# board.net
KiCad netlist of a schematic drawn in EAGLE
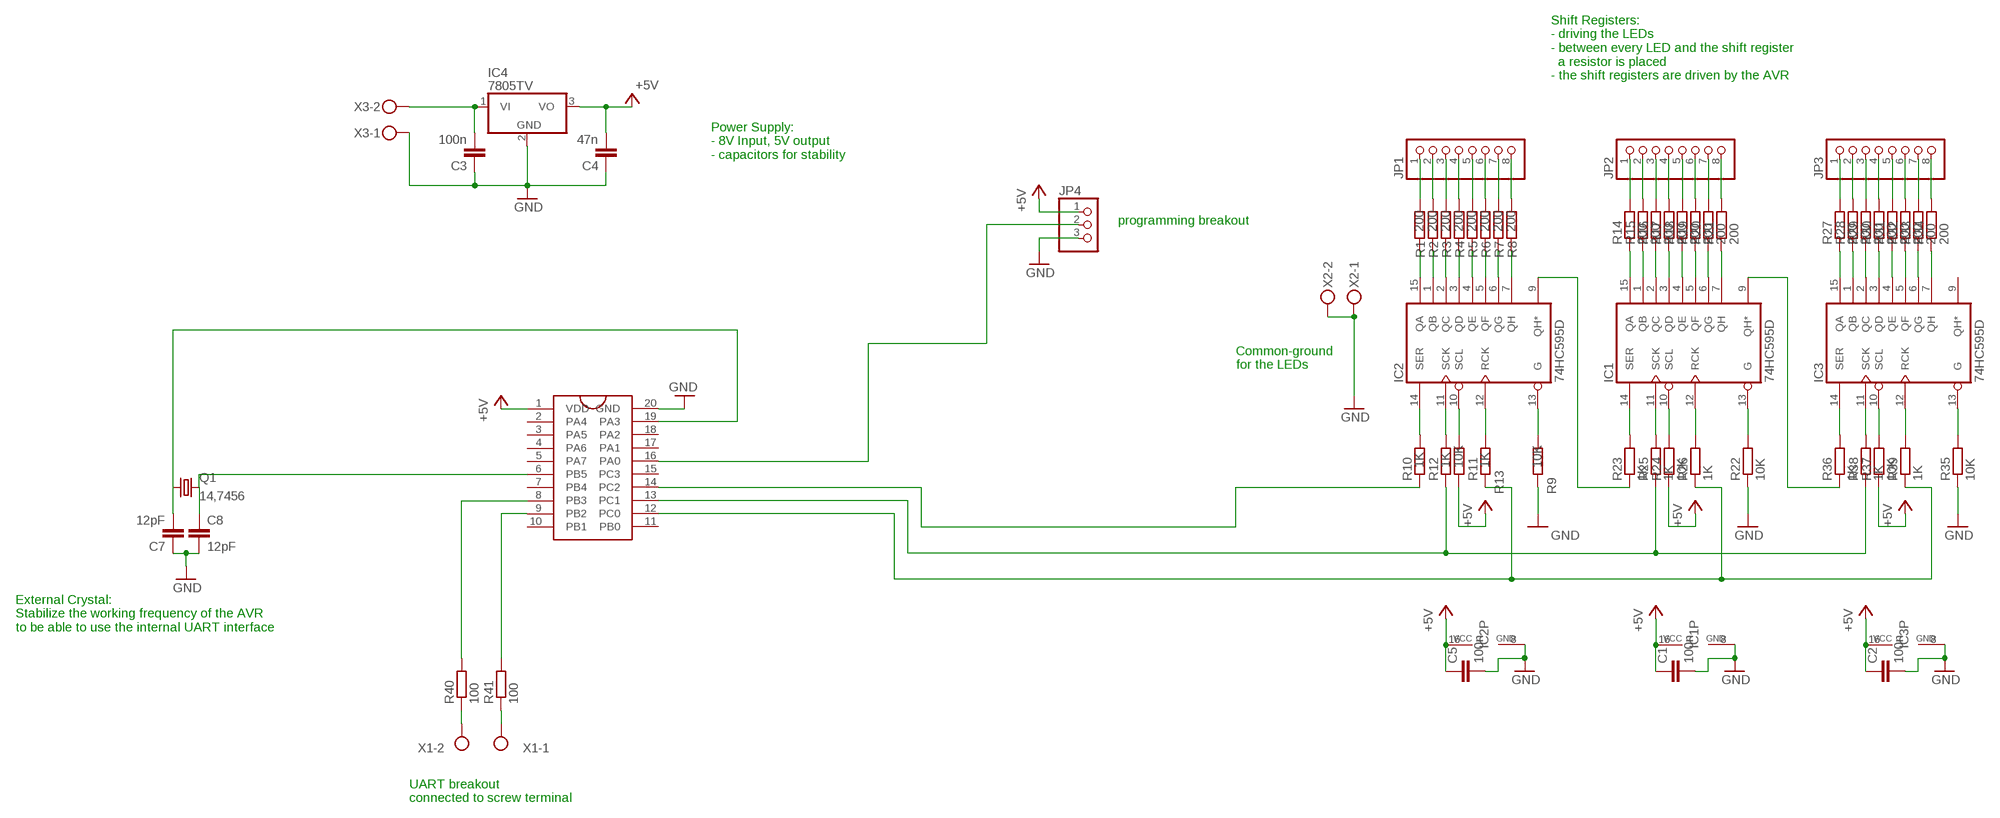
[diagram p0: schematic, sheet 1]

(export (version "E")
  (design (tool "Eeschema 10.0.6"))
  (components
    (comp (ref "C1")
      (value "100n")
      (footprint "eagle-import:C0805K")
      (libsource (lib "eagle-import") (part "C-EUC0805K"))
    )
    (comp (ref "C2")
      (value "100n")
      (footprint "eagle-import:C0805K")
      (libsource (lib "eagle-import") (part "C-EUC0805K"))
    )
    (comp (ref "C3")
      (value "100n")
      (footprint "eagle-import:C0805K")
      (libsource (lib "eagle-import") (part "C-EUC0805K"))
    )
    (comp (ref "C4")
      (value "47n")
      (footprint "eagle-import:C0805K")
      (libsource (lib "eagle-import") (part "C-EUC0805K"))
    )
    (comp (ref "C5")
      (value "100n")
      (footprint "eagle-import:C0805K")
      (libsource (lib "eagle-import") (part "C-EUC0805K"))
    )
    (comp (ref "C7")
      (value "12pF")
      (footprint "eagle-import:C0805K")
      (libsource (lib "eagle-import") (part "C-EUC0805K"))
    )
    (comp (ref "C8")
      (value "12pF")
      (footprint "eagle-import:C0805K")
      (libsource (lib "eagle-import") (part "C-EUC0805K"))
    )
    (comp (ref "IC1")
      (value "74HC595D")
      (footprint "eagle-import:SO16")
      (libsource (lib "eagle-import") (part "74595DHC"))
    )
    (comp (ref "IC2")
      (value "74HC595D")
      (footprint "eagle-import:SO16")
      (libsource (lib "eagle-import") (part "74595DHC"))
    )
    (comp (ref "IC3")
      (value "74HC595D")
      (footprint "eagle-import:SO16")
      (libsource (lib "eagle-import") (part "74595DHC"))
    )
    (comp (ref "IC4")
      (value "7805TV")
      (footprint "eagle-import:TO220V")
      (libsource (lib "eagle-import") (part "78TV05"))
    )
    (comp (ref "JP1")
      (value "PINHD-1X8")
      (footprint "eagle-import:1X08")
      (libsource (lib "eagle-import") (part "PINHD-1X8"))
    )
    (comp (ref "JP2")
      (value "PINHD-1X8")
      (footprint "eagle-import:1X08")
      (libsource (lib "eagle-import") (part "PINHD-1X8"))
    )
    (comp (ref "JP3")
      (value "PINHD-1X8")
      (footprint "eagle-import:1X08")
      (libsource (lib "eagle-import") (part "PINHD-1X8"))
    )
    (comp (ref "JP4")
      (value "PINHD-1X3")
      (footprint "eagle-import:1X03")
      (libsource (lib "eagle-import") (part "PINHD-1X3"))
    )
    (comp (ref "Q1")
      (value "14,7456")
      (footprint "eagle-import:SM49")
      (libsource (lib "eagle-import") (part "CRYSTALSM49"))
    )
    (comp (ref "R1")
      (value "200")
      (footprint "eagle-import:M0805")
      (libsource (lib "eagle-import") (part "R-EU_M0805"))
    )
    (comp (ref "R2")
      (value "200")
      (footprint "eagle-import:M0805")
      (libsource (lib "eagle-import") (part "R-EU_M0805"))
    )
    (comp (ref "R3")
      (value "200")
      (footprint "eagle-import:M0805")
      (libsource (lib "eagle-import") (part "R-EU_M0805"))
    )
    (comp (ref "R4")
      (value "200")
      (footprint "eagle-import:M0805")
      (libsource (lib "eagle-import") (part "R-EU_M0805"))
    )
    (comp (ref "R5")
      (value "200")
      (footprint "eagle-import:M0805")
      (libsource (lib "eagle-import") (part "R-EU_M0805"))
    )
    (comp (ref "R6")
      (value "200")
      (footprint "eagle-import:M0805")
      (libsource (lib "eagle-import") (part "R-EU_M0805"))
    )
    (comp (ref "R7")
      (value "200")
      (footprint "eagle-import:M0805")
      (libsource (lib "eagle-import") (part "R-EU_M0805"))
    )
    (comp (ref "R8")
      (value "200")
      (footprint "eagle-import:M0805")
      (libsource (lib "eagle-import") (part "R-EU_M0805"))
    )
    (comp (ref "R9")
      (value "10K")
      (footprint "eagle-import:M0805")
      (libsource (lib "eagle-import") (part "R-EU_M0805"))
    )
    (comp (ref "R10")
      (value "1K")
      (footprint "eagle-import:M0805")
      (libsource (lib "eagle-import") (part "R-EU_M0805"))
    )
    (comp (ref "R11")
      (value "10K")
      (footprint "eagle-import:M0805")
      (libsource (lib "eagle-import") (part "R-EU_M0805"))
    )
    (comp (ref "R12")
      (value "1K")
      (footprint "eagle-import:M0805")
      (libsource (lib "eagle-import") (part "R-EU_M0805"))
    )
    (comp (ref "R13")
      (value "1K")
      (footprint "eagle-import:M0805")
      (libsource (lib "eagle-import") (part "R-EU_M0805"))
    )
    (comp (ref "R14")
      (value "200")
      (footprint "eagle-import:M0805")
      (libsource (lib "eagle-import") (part "R-EU_M0805"))
    )
    (comp (ref "R15")
      (value "200")
      (footprint "eagle-import:M0805")
      (libsource (lib "eagle-import") (part "R-EU_M0805"))
    )
    (comp (ref "R16")
      (value "200")
      (footprint "eagle-import:M0805")
      (libsource (lib "eagle-import") (part "R-EU_M0805"))
    )
    (comp (ref "R17")
      (value "200")
      (footprint "eagle-import:M0805")
      (libsource (lib "eagle-import") (part "R-EU_M0805"))
    )
    (comp (ref "R18")
      (value "200")
      (footprint "eagle-import:M0805")
      (libsource (lib "eagle-import") (part "R-EU_M0805"))
    )
    (comp (ref "R19")
      (value "200")
      (footprint "eagle-import:M0805")
      (libsource (lib "eagle-import") (part "R-EU_M0805"))
    )
    (comp (ref "R20")
      (value "200")
      (footprint "eagle-import:M0805")
      (libsource (lib "eagle-import") (part "R-EU_M0805"))
    )
    (comp (ref "R21")
      (value "200")
      (footprint "eagle-import:M0805")
      (libsource (lib "eagle-import") (part "R-EU_M0805"))
    )
    (comp (ref "R22")
      (value "10K")
      (footprint "eagle-import:M0805")
      (libsource (lib "eagle-import") (part "R-EU_M0805"))
    )
    (comp (ref "R23")
      (value "1K")
      (footprint "eagle-import:M0805")
      (libsource (lib "eagle-import") (part "R-EU_M0805"))
    )
    (comp (ref "R24")
      (value "10K")
      (footprint "eagle-import:M0805")
      (libsource (lib "eagle-import") (part "R-EU_M0805"))
    )
    (comp (ref "R25")
      (value "1K")
      (footprint "eagle-import:M0805")
      (libsource (lib "eagle-import") (part "R-EU_M0805"))
    )
    (comp (ref "R26")
      (value "1K")
      (footprint "eagle-import:M0805")
      (libsource (lib "eagle-import") (part "R-EU_M0805"))
    )
    (comp (ref "R27")
      (value "200")
      (footprint "eagle-import:M0805")
      (libsource (lib "eagle-import") (part "R-EU_M0805"))
    )
    (comp (ref "R28")
      (value "200")
      (footprint "eagle-import:M0805")
      (libsource (lib "eagle-import") (part "R-EU_M0805"))
    )
    (comp (ref "R29")
      (value "200")
      (footprint "eagle-import:M0805")
      (libsource (lib "eagle-import") (part "R-EU_M0805"))
    )
    (comp (ref "R30")
      (value "200")
      (footprint "eagle-import:M0805")
      (libsource (lib "eagle-import") (part "R-EU_M0805"))
    )
    (comp (ref "R31")
      (value "200")
      (footprint "eagle-import:M0805")
      (libsource (lib "eagle-import") (part "R-EU_M0805"))
    )
    (comp (ref "R32")
      (value "200")
      (footprint "eagle-import:M0805")
      (libsource (lib "eagle-import") (part "R-EU_M0805"))
    )
    (comp (ref "R33")
      (value "200")
      (footprint "eagle-import:M0805")
      (libsource (lib "eagle-import") (part "R-EU_M0805"))
    )
    (comp (ref "R34")
      (value "200")
      (footprint "eagle-import:M0805")
      (libsource (lib "eagle-import") (part "R-EU_M0805"))
    )
    (comp (ref "R35")
      (value "10K")
      (footprint "eagle-import:M0805")
      (libsource (lib "eagle-import") (part "R-EU_M0805"))
    )
    (comp (ref "R36")
      (value "1K")
      (footprint "eagle-import:M0805")
      (libsource (lib "eagle-import") (part "R-EU_M0805"))
    )
    (comp (ref "R37")
      (value "10K")
      (footprint "eagle-import:M0805")
      (libsource (lib "eagle-import") (part "R-EU_M0805"))
    )
    (comp (ref "R38")
      (value "1K")
      (footprint "eagle-import:M0805")
      (libsource (lib "eagle-import") (part "R-EU_M0805"))
    )
    (comp (ref "R39")
      (value "1K")
      (footprint "eagle-import:M0805")
      (libsource (lib "eagle-import") (part "R-EU_M0805"))
    )
    (comp (ref "R40")
      (value "100")
      (footprint "eagle-import:M0805")
      (libsource (lib "eagle-import") (part "R-EU_M0805"))
    )
    (comp (ref "R41")
      (value "100")
      (footprint "eagle-import:M0805")
      (libsource (lib "eagle-import") (part "R-EU_M0805"))
    )
    (comp (ref "U$1")
      (value "ATTINY406")
      (footprint "eagle-import:SO20L")
      (libsource (lib "eagle-import") (part "ATTINY406"))
    )
    (comp (ref "X1")
      (value "MKDSN1,5/2-5,08")
      (footprint "eagle-import:MKDSN1,5_2-5,08")
      (libsource (lib "eagle-import") (part "MKDSN1,5/2-5,08"))
    )
    (comp (ref "X2")
      (value "MKDSN1,5/2-5,08")
      (footprint "eagle-import:MKDSN1,5_2-5,08")
      (libsource (lib "eagle-import") (part "MKDSN1,5/2-5,08"))
    )
    (comp (ref "X3")
      (value "MKDSN1,5/2-5,08")
      (footprint "eagle-import:MKDSN1,5_2-5,08")
      (libsource (lib "eagle-import") (part "MKDSN1,5/2-5,08"))
    )
  )
  (nets
    (net (code "1") (name "+5V") (class "Default")
      (node (ref "C1") (pin "1") (pinfunction "1_1") (pintype "passive"))
      (node (ref "C2") (pin "1") (pinfunction "1_1") (pintype "passive"))
      (node (ref "C4") (pin "2") (pinfunction "2_2") (pintype "passive"))
      (node (ref "C5") (pin "1") (pinfunction "1_1") (pintype "passive"))
      (node (ref "IC1") (pin "16") (pinfunction "VCC_16") (pintype "power_in"))
      (node (ref "IC2") (pin "16") (pinfunction "VCC_16") (pintype "power_in"))
      (node (ref "IC3") (pin "16") (pinfunction "VCC_16") (pintype "power_in"))
      (node (ref "IC4") (pin "3") (pinfunction "VO_3") (pintype "passive"))
      (node (ref "JP4") (pin "1") (pinfunction "1_1") (pintype "passive"))
      (node (ref "R11") (pin "1") (pinfunction "1_1") (pintype "passive"))
      (node (ref "R24") (pin "1") (pinfunction "1_1") (pintype "passive"))
      (node (ref "R37") (pin "1") (pinfunction "1_1") (pintype "passive"))
      (node (ref "U$1") (pin "1") (pinfunction "VDD_1") (pintype "bidirectional"))
    )
    (net (code "2") (name "GND") (class "Default")
      (node (ref "C1") (pin "2") (pinfunction "2_2") (pintype "passive"))
      (node (ref "C2") (pin "2") (pinfunction "2_2") (pintype "passive"))
      (node (ref "C3") (pin "1") (pinfunction "1_1") (pintype "passive"))
      (node (ref "C4") (pin "1") (pinfunction "1_1") (pintype "passive"))
      (node (ref "C5") (pin "2") (pinfunction "2_2") (pintype "passive"))
      (node (ref "C7") (pin "1") (pinfunction "1_1") (pintype "passive"))
      (node (ref "C8") (pin "2") (pinfunction "2_2") (pintype "passive"))
      (node (ref "IC1") (pin "8") (pinfunction "GND_8") (pintype "power_in"))
      (node (ref "IC2") (pin "8") (pinfunction "GND_8") (pintype "power_in"))
      (node (ref "IC3") (pin "8") (pinfunction "GND_8") (pintype "power_in"))
      (node (ref "IC4") (pin "2") (pinfunction "GND_2") (pintype "passive"))
      (node (ref "JP4") (pin "3") (pinfunction "3_3") (pintype "passive"))
      (node (ref "R22") (pin "1") (pinfunction "1_1") (pintype "passive"))
      (node (ref "R35") (pin "1") (pinfunction "1_1") (pintype "passive"))
      (node (ref "R9") (pin "1") (pinfunction "1_1") (pintype "passive"))
      (node (ref "U$1") (pin "20") (pinfunction "GND_20") (pintype "bidirectional"))
      (node (ref "X2") (pin "1") (pinfunction "KL_1") (pintype "passive"))
      (node (ref "X2") (pin "2") (pinfunction "KL_2") (pintype "passive"))
      (node (ref "X3") (pin "1") (pinfunction "KL_1") (pintype "passive"))
    )
    (net (code "3") (name "Net-(IC1A-G)") (class "Default")
      (node (ref "IC1") (pin "13") (pinfunction "G_13") (pintype "input"))
      (node (ref "R22") (pin "2") (pinfunction "2_2") (pintype "passive"))
    )
    (net (code "4") (name "Net-(IC1A-QA)") (class "Default")
      (node (ref "IC1") (pin "15") (pinfunction "QA_15") (pintype "tri_state"))
      (node (ref "R14") (pin "1") (pinfunction "1_1") (pintype "passive"))
    )
    (net (code "5") (name "Net-(IC1A-QB)") (class "Default")
      (node (ref "IC1") (pin "1") (pinfunction "QB_1") (pintype "tri_state"))
      (node (ref "R15") (pin "1") (pinfunction "1_1") (pintype "passive"))
    )
    (net (code "6") (name "Net-(IC1A-QC)") (class "Default")
      (node (ref "IC1") (pin "2") (pinfunction "QC_2") (pintype "tri_state"))
      (node (ref "R16") (pin "1") (pinfunction "1_1") (pintype "passive"))
    )
    (net (code "7") (name "Net-(IC1A-QD)") (class "Default")
      (node (ref "IC1") (pin "3") (pinfunction "QD_3") (pintype "tri_state"))
      (node (ref "R17") (pin "1") (pinfunction "1_1") (pintype "passive"))
    )
    (net (code "8") (name "Net-(IC1A-QE)") (class "Default")
      (node (ref "IC1") (pin "4") (pinfunction "QE_4") (pintype "tri_state"))
      (node (ref "R18") (pin "1") (pinfunction "1_1") (pintype "passive"))
    )
    (net (code "9") (name "Net-(IC1A-QF)") (class "Default")
      (node (ref "IC1") (pin "5") (pinfunction "QF_5") (pintype "tri_state"))
      (node (ref "R19") (pin "1") (pinfunction "1_1") (pintype "passive"))
    )
    (net (code "10") (name "Net-(IC1A-QG)") (class "Default")
      (node (ref "IC1") (pin "6") (pinfunction "QG_6") (pintype "tri_state"))
      (node (ref "R20") (pin "1") (pinfunction "1_1") (pintype "passive"))
    )
    (net (code "11") (name "Net-(IC1A-QH)") (class "Default")
      (node (ref "IC1") (pin "7") (pinfunction "QH_7") (pintype "tri_state"))
      (node (ref "R21") (pin "1") (pinfunction "1_1") (pintype "passive"))
    )
    (net (code "12") (name "Net-(IC1A-QH*)") (class "Default")
      (node (ref "IC1") (pin "9") (pinfunction "QH*_9") (pintype "tri_state"))
      (node (ref "R36") (pin "1") (pinfunction "1_1") (pintype "passive"))
    )
    (net (code "13") (name "Net-(IC1A-RCK)") (class "Default")
      (node (ref "IC1") (pin "12") (pinfunction "RCK_12") (pintype "input"))
      (node (ref "R26") (pin "2") (pinfunction "2_2") (pintype "passive"))
    )
    (net (code "14") (name "Net-(IC1A-SCK)") (class "Default")
      (node (ref "IC1") (pin "11") (pinfunction "SCK_11") (pintype "input"))
      (node (ref "R25") (pin "2") (pinfunction "2_2") (pintype "passive"))
    )
    (net (code "15") (name "Net-(IC1A-SCL)") (class "Default")
      (node (ref "IC1") (pin "10") (pinfunction "SCL_10") (pintype "input"))
      (node (ref "R24") (pin "2") (pinfunction "2_2") (pintype "passive"))
    )
    (net (code "16") (name "Net-(IC1A-SER)") (class "Default")
      (node (ref "IC1") (pin "14") (pinfunction "SER_14") (pintype "input"))
      (node (ref "R23") (pin "2") (pinfunction "2_2") (pintype "passive"))
    )
    (net (code "17") (name "Net-(IC2A-G)") (class "Default")
      (node (ref "IC2") (pin "13") (pinfunction "G_13") (pintype "input"))
      (node (ref "R9") (pin "2") (pinfunction "2_2") (pintype "passive"))
    )
    (net (code "18") (name "Net-(IC2A-QA)") (class "Default")
      (node (ref "IC2") (pin "15") (pinfunction "QA_15") (pintype "tri_state"))
      (node (ref "R1") (pin "1") (pinfunction "1_1") (pintype "passive"))
    )
    (net (code "19") (name "Net-(IC2A-QB)") (class "Default")
      (node (ref "IC2") (pin "1") (pinfunction "QB_1") (pintype "tri_state"))
      (node (ref "R2") (pin "1") (pinfunction "1_1") (pintype "passive"))
    )
    (net (code "20") (name "Net-(IC2A-QC)") (class "Default")
      (node (ref "IC2") (pin "2") (pinfunction "QC_2") (pintype "tri_state"))
      (node (ref "R3") (pin "1") (pinfunction "1_1") (pintype "passive"))
    )
    (net (code "21") (name "Net-(IC2A-QD)") (class "Default")
      (node (ref "IC2") (pin "3") (pinfunction "QD_3") (pintype "tri_state"))
      (node (ref "R4") (pin "1") (pinfunction "1_1") (pintype "passive"))
    )
    (net (code "22") (name "Net-(IC2A-QE)") (class "Default")
      (node (ref "IC2") (pin "4") (pinfunction "QE_4") (pintype "tri_state"))
      (node (ref "R5") (pin "1") (pinfunction "1_1") (pintype "passive"))
    )
    (net (code "23") (name "Net-(IC2A-QF)") (class "Default")
      (node (ref "IC2") (pin "5") (pinfunction "QF_5") (pintype "tri_state"))
      (node (ref "R6") (pin "1") (pinfunction "1_1") (pintype "passive"))
    )
    (net (code "24") (name "Net-(IC2A-QG)") (class "Default")
      (node (ref "IC2") (pin "6") (pinfunction "QG_6") (pintype "tri_state"))
      (node (ref "R7") (pin "1") (pinfunction "1_1") (pintype "passive"))
    )
    (net (code "25") (name "Net-(IC2A-QH)") (class "Default")
      (node (ref "IC2") (pin "7") (pinfunction "QH_7") (pintype "tri_state"))
      (node (ref "R8") (pin "1") (pinfunction "1_1") (pintype "passive"))
    )
    (net (code "26") (name "Net-(IC2A-QH*)") (class "Default")
      (node (ref "IC2") (pin "9") (pinfunction "QH*_9") (pintype "tri_state"))
      (node (ref "R23") (pin "1") (pinfunction "1_1") (pintype "passive"))
    )
    (net (code "27") (name "Net-(IC2A-RCK)") (class "Default")
      (node (ref "IC2") (pin "12") (pinfunction "RCK_12") (pintype "input"))
      (node (ref "R13") (pin "2") (pinfunction "2_2") (pintype "passive"))
    )
    (net (code "28") (name "Net-(IC2A-SCK)") (class "Default")
      (node (ref "IC2") (pin "11") (pinfunction "SCK_11") (pintype "input"))
      (node (ref "R12") (pin "2") (pinfunction "2_2") (pintype "passive"))
    )
    (net (code "29") (name "Net-(IC2A-SCL)") (class "Default")
      (node (ref "IC2") (pin "10") (pinfunction "SCL_10") (pintype "input"))
      (node (ref "R11") (pin "2") (pinfunction "2_2") (pintype "passive"))
    )
    (net (code "30") (name "Net-(IC2A-SER)") (class "Default")
      (node (ref "IC2") (pin "14") (pinfunction "SER_14") (pintype "input"))
      (node (ref "R10") (pin "2") (pinfunction "2_2") (pintype "passive"))
    )
    (net (code "31") (name "Net-(IC3A-G)") (class "Default")
      (node (ref "IC3") (pin "13") (pinfunction "G_13") (pintype "input"))
      (node (ref "R35") (pin "2") (pinfunction "2_2") (pintype "passive"))
    )
    (net (code "32") (name "Net-(IC3A-QA)") (class "Default")
      (node (ref "IC3") (pin "15") (pinfunction "QA_15") (pintype "tri_state"))
      (node (ref "R27") (pin "1") (pinfunction "1_1") (pintype "passive"))
    )
    (net (code "33") (name "Net-(IC3A-QB)") (class "Default")
      (node (ref "IC3") (pin "1") (pinfunction "QB_1") (pintype "tri_state"))
      (node (ref "R28") (pin "1") (pinfunction "1_1") (pintype "passive"))
    )
    (net (code "34") (name "Net-(IC3A-QC)") (class "Default")
      (node (ref "IC3") (pin "2") (pinfunction "QC_2") (pintype "tri_state"))
      (node (ref "R29") (pin "1") (pinfunction "1_1") (pintype "passive"))
    )
    (net (code "35") (name "Net-(IC3A-QD)") (class "Default")
      (node (ref "IC3") (pin "3") (pinfunction "QD_3") (pintype "tri_state"))
      (node (ref "R30") (pin "1") (pinfunction "1_1") (pintype "passive"))
    )
    (net (code "36") (name "Net-(IC3A-QE)") (class "Default")
      (node (ref "IC3") (pin "4") (pinfunction "QE_4") (pintype "tri_state"))
      (node (ref "R31") (pin "1") (pinfunction "1_1") (pintype "passive"))
    )
    (net (code "37") (name "Net-(IC3A-QF)") (class "Default")
      (node (ref "IC3") (pin "5") (pinfunction "QF_5") (pintype "tri_state"))
      (node (ref "R32") (pin "1") (pinfunction "1_1") (pintype "passive"))
    )
    (net (code "38") (name "Net-(IC3A-QG)") (class "Default")
      (node (ref "IC3") (pin "6") (pinfunction "QG_6") (pintype "tri_state"))
      (node (ref "R33") (pin "1") (pinfunction "1_1") (pintype "passive"))
    )
    (net (code "39") (name "Net-(IC3A-QH)") (class "Default")
      (node (ref "IC3") (pin "7") (pinfunction "QH_7") (pintype "tri_state"))
      (node (ref "R34") (pin "1") (pinfunction "1_1") (pintype "passive"))
    )
    (net (code "40") (name "Net-(IC3A-RCK)") (class "Default")
      (node (ref "IC3") (pin "12") (pinfunction "RCK_12") (pintype "input"))
      (node (ref "R39") (pin "2") (pinfunction "2_2") (pintype "passive"))
    )
    (net (code "41") (name "Net-(IC3A-SCK)") (class "Default")
      (node (ref "IC3") (pin "11") (pinfunction "SCK_11") (pintype "input"))
      (node (ref "R38") (pin "2") (pinfunction "2_2") (pintype "passive"))
    )
    (net (code "42") (name "Net-(IC3A-SCL)") (class "Default")
      (node (ref "IC3") (pin "10") (pinfunction "SCL_10") (pintype "input"))
      (node (ref "R37") (pin "2") (pinfunction "2_2") (pintype "passive"))
    )
    (net (code "43") (name "Net-(IC3A-SER)") (class "Default")
      (node (ref "IC3") (pin "14") (pinfunction "SER_14") (pintype "input"))
      (node (ref "R36") (pin "2") (pinfunction "2_2") (pintype "passive"))
    )
    (net (code "44") (name "Net-(IC4-VI)") (class "Default")
      (node (ref "C3") (pin "2") (pinfunction "2_2") (pintype "passive"))
      (node (ref "IC4") (pin "1") (pinfunction "VI_1") (pintype "input"))
      (node (ref "X3") (pin "2") (pinfunction "KL_2") (pintype "passive"))
    )
    (net (code "45") (name "Net-(JP1-Pad1)") (class "Default")
      (node (ref "JP1") (pin "1") (pinfunction "1_1") (pintype "passive"))
      (node (ref "R1") (pin "2") (pinfunction "2_2") (pintype "passive"))
    )
    (net (code "46") (name "Net-(JP1-Pad2)") (class "Default")
      (node (ref "JP1") (pin "2") (pinfunction "2_2") (pintype "passive"))
      (node (ref "R2") (pin "2") (pinfunction "2_2") (pintype "passive"))
    )
    (net (code "47") (name "Net-(JP1-Pad3)") (class "Default")
      (node (ref "JP1") (pin "3") (pinfunction "3_3") (pintype "passive"))
      (node (ref "R3") (pin "2") (pinfunction "2_2") (pintype "passive"))
    )
    (net (code "48") (name "Net-(JP1-Pad4)") (class "Default")
      (node (ref "JP1") (pin "4") (pinfunction "4_4") (pintype "passive"))
      (node (ref "R4") (pin "2") (pinfunction "2_2") (pintype "passive"))
    )
    (net (code "49") (name "Net-(JP1-Pad5)") (class "Default")
      (node (ref "JP1") (pin "5") (pinfunction "5_5") (pintype "passive"))
      (node (ref "R5") (pin "2") (pinfunction "2_2") (pintype "passive"))
    )
    (net (code "50") (name "Net-(JP1-Pad6)") (class "Default")
      (node (ref "JP1") (pin "6") (pinfunction "6_6") (pintype "passive"))
      (node (ref "R6") (pin "2") (pinfunction "2_2") (pintype "passive"))
    )
    (net (code "51") (name "Net-(JP1-Pad7)") (class "Default")
      (node (ref "JP1") (pin "7") (pinfunction "7_7") (pintype "passive"))
      (node (ref "R7") (pin "2") (pinfunction "2_2") (pintype "passive"))
    )
    (net (code "52") (name "Net-(JP1-Pad8)") (class "Default")
      (node (ref "JP1") (pin "8") (pinfunction "8_8") (pintype "passive"))
      (node (ref "R8") (pin "2") (pinfunction "2_2") (pintype "passive"))
    )
    (net (code "53") (name "Net-(JP2-Pad1)") (class "Default")
      (node (ref "JP2") (pin "1") (pinfunction "1_1") (pintype "passive"))
      (node (ref "R14") (pin "2") (pinfunction "2_2") (pintype "passive"))
    )
    (net (code "54") (name "Net-(JP2-Pad2)") (class "Default")
      (node (ref "JP2") (pin "2") (pinfunction "2_2") (pintype "passive"))
      (node (ref "R15") (pin "2") (pinfunction "2_2") (pintype "passive"))
    )
    (net (code "55") (name "Net-(JP2-Pad3)") (class "Default")
      (node (ref "JP2") (pin "3") (pinfunction "3_3") (pintype "passive"))
      (node (ref "R16") (pin "2") (pinfunction "2_2") (pintype "passive"))
    )
    (net (code "56") (name "Net-(JP2-Pad4)") (class "Default")
      (node (ref "JP2") (pin "4") (pinfunction "4_4") (pintype "passive"))
      (node (ref "R17") (pin "2") (pinfunction "2_2") (pintype "passive"))
    )
    (net (code "57") (name "Net-(JP2-Pad5)") (class "Default")
      (node (ref "JP2") (pin "5") (pinfunction "5_5") (pintype "passive"))
      (node (ref "R18") (pin "2") (pinfunction "2_2") (pintype "passive"))
    )
    (net (code "58") (name "Net-(JP2-Pad6)") (class "Default")
      (node (ref "JP2") (pin "6") (pinfunction "6_6") (pintype "passive"))
      (node (ref "R19") (pin "2") (pinfunction "2_2") (pintype "passive"))
    )
    (net (code "59") (name "Net-(JP2-Pad7)") (class "Default")
      (node (ref "JP2") (pin "7") (pinfunction "7_7") (pintype "passive"))
      (node (ref "R20") (pin "2") (pinfunction "2_2") (pintype "passive"))
    )
    (net (code "60") (name "Net-(JP2-Pad8)") (class "Default")
      (node (ref "JP2") (pin "8") (pinfunction "8_8") (pintype "passive"))
      (node (ref "R21") (pin "2") (pinfunction "2_2") (pintype "passive"))
    )
    (net (code "61") (name "Net-(JP3-Pad1)") (class "Default")
      (node (ref "JP3") (pin "1") (pinfunction "1_1") (pintype "passive"))
      (node (ref "R27") (pin "2") (pinfunction "2_2") (pintype "passive"))
    )
    (net (code "62") (name "Net-(JP3-Pad2)") (class "Default")
      (node (ref "JP3") (pin "2") (pinfunction "2_2") (pintype "passive"))
      (node (ref "R28") (pin "2") (pinfunction "2_2") (pintype "passive"))
    )
    (net (code "63") (name "Net-(JP3-Pad3)") (class "Default")
      (node (ref "JP3") (pin "3") (pinfunction "3_3") (pintype "passive"))
      (node (ref "R29") (pin "2") (pinfunction "2_2") (pintype "passive"))
    )
    (net (code "64") (name "Net-(JP3-Pad4)") (class "Default")
      (node (ref "JP3") (pin "4") (pinfunction "4_4") (pintype "passive"))
      (node (ref "R30") (pin "2") (pinfunction "2_2") (pintype "passive"))
    )
    (net (code "65") (name "Net-(JP3-Pad5)") (class "Default")
      (node (ref "JP3") (pin "5") (pinfunction "5_5") (pintype "passive"))
      (node (ref "R31") (pin "2") (pinfunction "2_2") (pintype "passive"))
    )
    (net (code "66") (name "Net-(JP3-Pad6)") (class "Default")
      (node (ref "JP3") (pin "6") (pinfunction "6_6") (pintype "passive"))
      (node (ref "R32") (pin "2") (pinfunction "2_2") (pintype "passive"))
    )
    (net (code "67") (name "Net-(JP3-Pad7)") (class "Default")
      (node (ref "JP3") (pin "7") (pinfunction "7_7") (pintype "passive"))
      (node (ref "R33") (pin "2") (pinfunction "2_2") (pintype "passive"))
    )
    (net (code "68") (name "Net-(JP3-Pad8)") (class "Default")
      (node (ref "JP3") (pin "8") (pinfunction "8_8") (pintype "passive"))
      (node (ref "R34") (pin "2") (pinfunction "2_2") (pintype "passive"))
    )
    (net (code "69") (name "Net-(U$1-PA0)") (class "Default")
      (node (ref "JP4") (pin "2") (pinfunction "2_2") (pintype "passive"))
      (node (ref "U$1") (pin "16") (pinfunction "PA0_16") (pintype "bidirectional"))
    )
    (net (code "70") (name "Net-(U$1-PA3)") (class "Default")
      (node (ref "C7") (pin "2") (pinfunction "2_2") (pintype "passive"))
      (node (ref "Q1") (pin "1") (pinfunction "1_1") (pintype "passive"))
      (node (ref "U$1") (pin "19") (pinfunction "PA3_19") (pintype "bidirectional"))
    )
    (net (code "71") (name "Net-(U$1-PB2)") (class "Default")
      (node (ref "R41") (pin "2") (pinfunction "2_2") (pintype "passive"))
      (node (ref "U$1") (pin "9") (pinfunction "PB2_9") (pintype "bidirectional"))
    )
    (net (code "72") (name "Net-(U$1-PB3)") (class "Default")
      (node (ref "R40") (pin "2") (pinfunction "2_2") (pintype "passive"))
      (node (ref "U$1") (pin "8") (pinfunction "PB3_8") (pintype "bidirectional"))
    )
    (net (code "73") (name "Net-(U$1-PB5)") (class "Default")
      (node (ref "C8") (pin "1") (pinfunction "1_1") (pintype "passive"))
      (node (ref "Q1") (pin "2") (pinfunction "2_2") (pintype "passive"))
      (node (ref "U$1") (pin "6") (pinfunction "PB5_6") (pintype "bidirectional"))
    )
    (net (code "74") (name "Net-(U$1-PC0)") (class "Default")
      (node (ref "R13") (pin "1") (pinfunction "1_1") (pintype "passive"))
      (node (ref "R26") (pin "1") (pinfunction "1_1") (pintype "passive"))
      (node (ref "R39") (pin "1") (pinfunction "1_1") (pintype "passive"))
      (node (ref "U$1") (pin "12") (pinfunction "PC0_12") (pintype "bidirectional"))
    )
    (net (code "75") (name "Net-(U$1-PC1)") (class "Default")
      (node (ref "R12") (pin "1") (pinfunction "1_1") (pintype "passive"))
      (node (ref "R25") (pin "1") (pinfunction "1_1") (pintype "passive"))
      (node (ref "R38") (pin "1") (pinfunction "1_1") (pintype "passive"))
      (node (ref "U$1") (pin "13") (pinfunction "PC1_13") (pintype "bidirectional"))
    )
    (net (code "76") (name "Net-(U$1-PC2)") (class "Default")
      (node (ref "R10") (pin "1") (pinfunction "1_1") (pintype "passive"))
      (node (ref "U$1") (pin "14") (pinfunction "PC2_14") (pintype "bidirectional"))
    )
    (net (code "77") (name "Net-(X1A-KL)") (class "Default")
      (node (ref "R41") (pin "1") (pinfunction "1_1") (pintype "passive"))
      (node (ref "X1") (pin "1") (pinfunction "KL_1") (pintype "passive"))
    )
    (net (code "78") (name "Net-(X1B-KL)") (class "Default")
      (node (ref "R40") (pin "1") (pinfunction "1_1") (pintype "passive"))
      (node (ref "X1") (pin "2") (pinfunction "KL_2") (pintype "passive"))
    )
    (net (code "79") (name "unconnected-(IC3A-QH*-Pad9)") (class "Default")
      (node (ref "IC3") (pin "9") (pinfunction "QH*_9") (pintype "tri_state"))
    )
    (net (code "80") (name "unconnected-(U$1-PA1-Pad17)") (class "Default")
      (node (ref "U$1") (pin "17") (pinfunction "PA1_17") (pintype "bidirectional"))
    )
    (net (code "81") (name "unconnected-(U$1-PA2-Pad18)") (class "Default")
      (node (ref "U$1") (pin "18") (pinfunction "PA2_18") (pintype "bidirectional"))
    )
    (net (code "82") (name "unconnected-(U$1-PA4-Pad2)") (class "Default")
      (node (ref "U$1") (pin "2") (pinfunction "PA4_2") (pintype "bidirectional"))
    )
    (net (code "83") (name "unconnected-(U$1-PA5-Pad3)") (class "Default")
      (node (ref "U$1") (pin "3") (pinfunction "PA5_3") (pintype "bidirectional"))
    )
    (net (code "84") (name "unconnected-(U$1-PA6-Pad4)") (class "Default")
      (node (ref "U$1") (pin "4") (pinfunction "PA6_4") (pintype "bidirectional"))
    )
    (net (code "85") (name "unconnected-(U$1-PA7-Pad5)") (class "Default")
      (node (ref "U$1") (pin "5") (pinfunction "PA7_5") (pintype "bidirectional"))
    )
    (net (code "86") (name "unconnected-(U$1-PB0-Pad11)") (class "Default")
      (node (ref "U$1") (pin "11") (pinfunction "PB0_11") (pintype "bidirectional"))
    )
    (net (code "87") (name "unconnected-(U$1-PB1-Pad10)") (class "Default")
      (node (ref "U$1") (pin "10") (pinfunction "PB1_10") (pintype "bidirectional"))
    )
    (net (code "88") (name "unconnected-(U$1-PB4-Pad7)") (class "Default")
      (node (ref "U$1") (pin "7") (pinfunction "PB4_7") (pintype "bidirectional"))
    )
    (net (code "89") (name "unconnected-(U$1-PC3-Pad15)") (class "Default")
      (node (ref "U$1") (pin "15") (pinfunction "PC3_15") (pintype "bidirectional"))
    )
  )
)
